# power.net
KiCad netlist of a schematic drawn in EAGLE
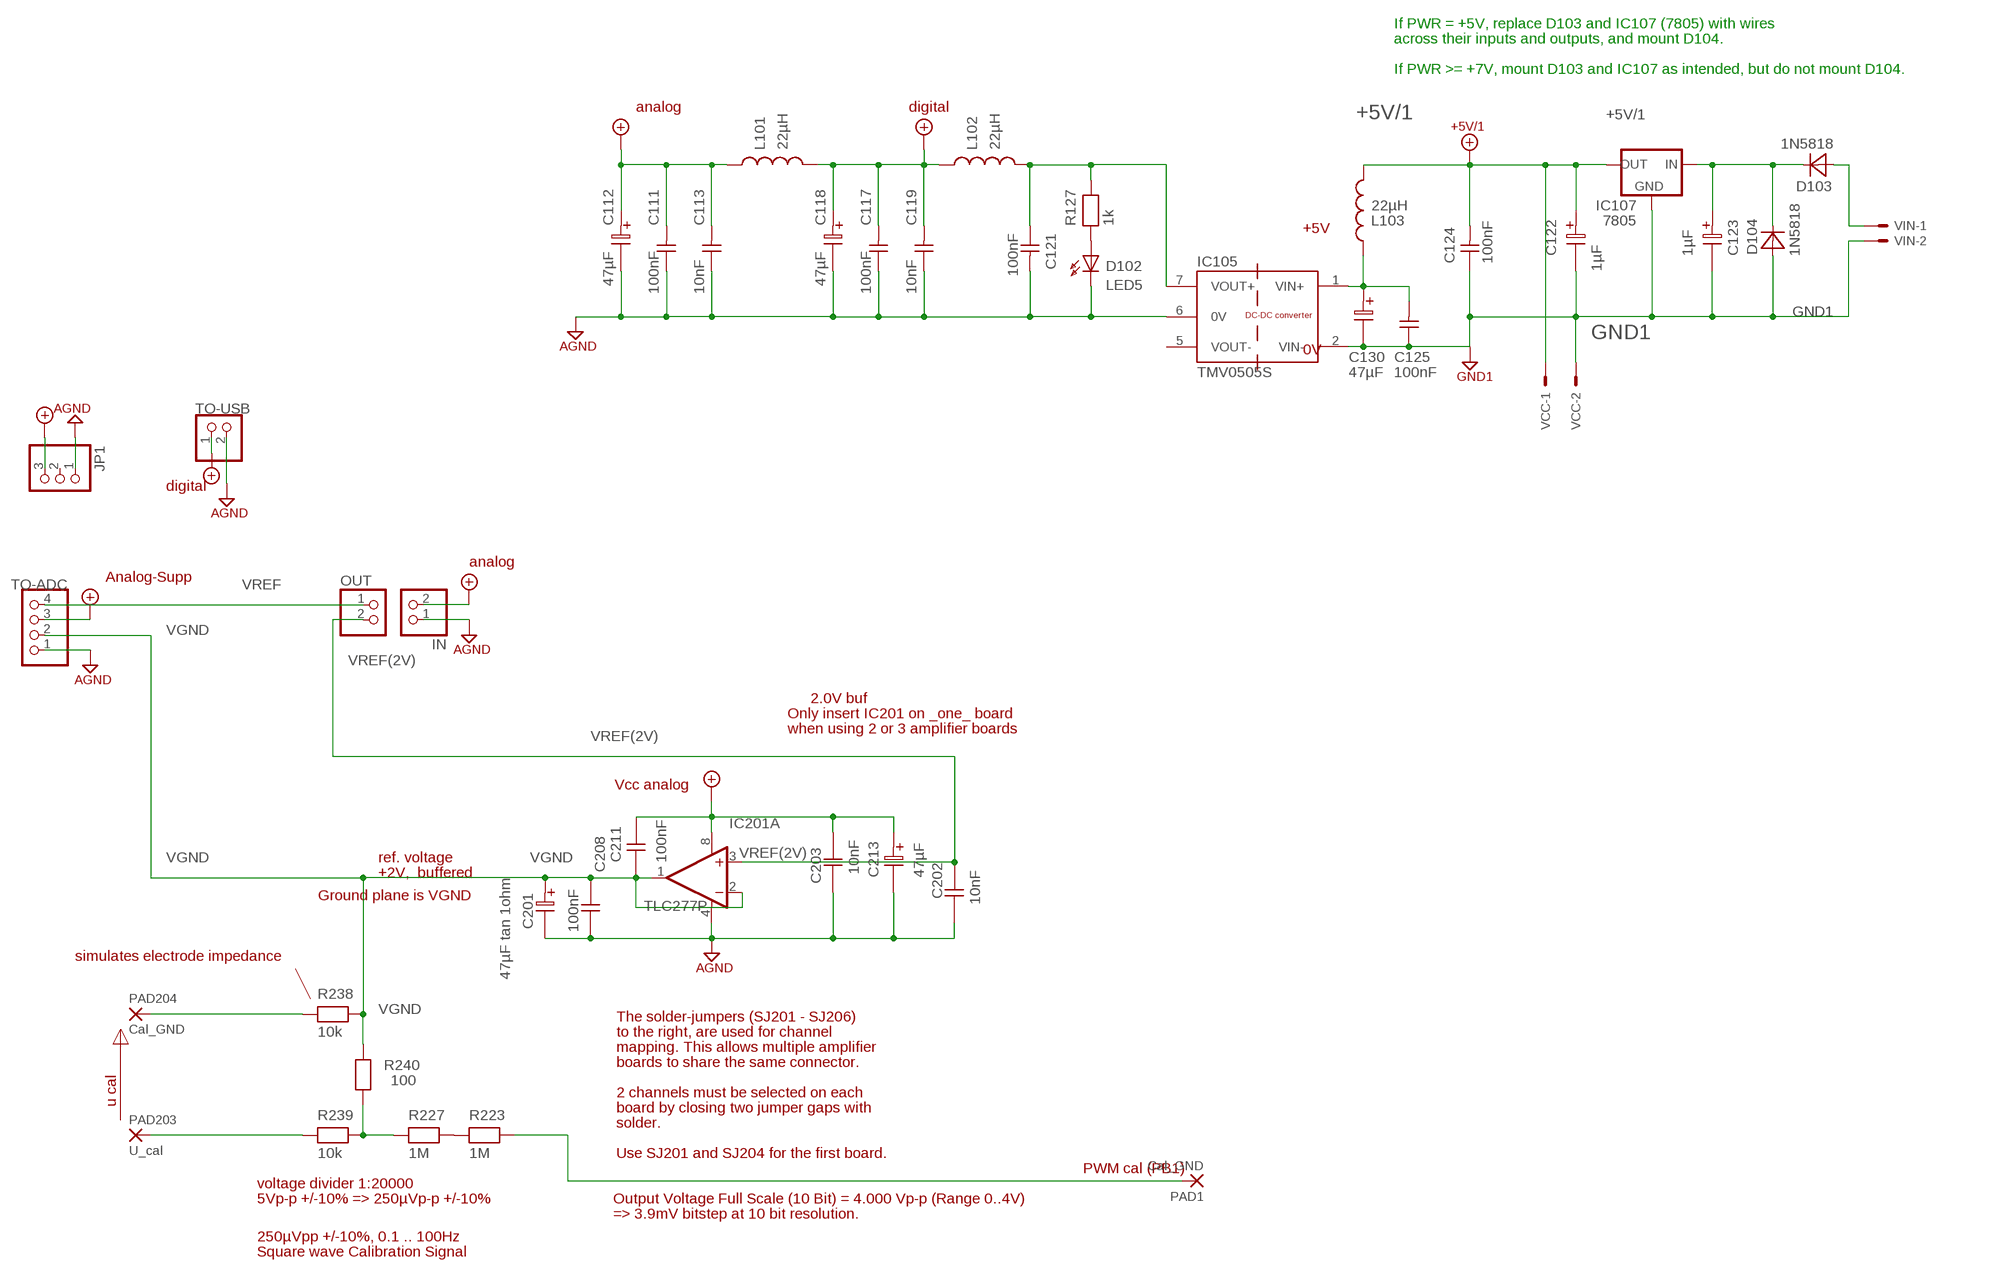
[diagram p0: schematic, sheet 1]

(export (version "E")
  (design (tool "Eeschema 10.0.6"))
  (components
    (comp (ref "C111")
      (value "100nF")
      (footprint "eagle-import:C-5")
      (libsource (lib "eagle-import") (part "CAPNP-5"))
    )
    (comp (ref "C112")
      (value "47µF")
      (footprint "eagle-import:EL25B")
      (libsource (lib "eagle-import") (part "discrete_211_ELC-5"))
    )
    (comp (ref "C113")
      (value "10nF")
      (footprint "eagle-import:C-5")
      (libsource (lib "eagle-import") (part "CAPNP-5"))
    )
    (comp (ref "C117")
      (value "100nF")
      (footprint "eagle-import:C-5")
      (libsource (lib "eagle-import") (part "CAPNP-5"))
    )
    (comp (ref "C118")
      (value "47µF")
      (footprint "eagle-import:EL25B")
      (libsource (lib "eagle-import") (part "discrete_211_ELC-5"))
    )
    (comp (ref "C119")
      (value "10nF")
      (footprint "eagle-import:C-5")
      (libsource (lib "eagle-import") (part "CAPNP-5"))
    )
    (comp (ref "C121")
      (value "100nF")
      (footprint "eagle-import:C-5@1")
      (libsource (lib "eagle-import") (part "discrete_211_CAPNP-5@2"))
    )
    (comp (ref "C122")
      (value "1µF")
      (footprint "eagle-import:EL25B")
      (libsource (lib "eagle-import") (part "ELC-2,5"))
    )
    (comp (ref "C123")
      (value "1µF")
      (footprint "eagle-import:EL25B")
      (libsource (lib "eagle-import") (part "ELC-2,5"))
    )
    (comp (ref "C124")
      (value "100nF")
      (footprint "eagle-import:C-5@1")
      (libsource (lib "eagle-import") (part "discrete_211_CAPNP-5@2"))
    )
    (comp (ref "C125")
      (value "100nF")
      (footprint "eagle-import:C-5")
      (libsource (lib "eagle-import") (part "CAPNP-5"))
    )
    (comp (ref "C130")
      (value "47µF")
      (footprint "eagle-import:EL25B")
      (libsource (lib "eagle-import") (part "discrete_211_ELC-5"))
    )
    (comp (ref "C201")
      (value "47µF tan 1ohm")
      (footprint "eagle-import:EL25B")
      (libsource (lib "eagle-import") (part "DISCRETE@3_ELC-2,5"))
    )
    (comp (ref "C202")
      (value "10nF")
      (footprint "eagle-import:C-5")
      (libsource (lib "eagle-import") (part "CAPNP-5@2"))
    )
    (comp (ref "C203")
      (value "10nF")
      (footprint "eagle-import:C-5")
      (libsource (lib "eagle-import") (part "CAPNP-7,5"))
    )
    (comp (ref "C208")
      (value "100nF")
      (footprint "eagle-import:C-5")
      (libsource (lib "eagle-import") (part "CAPNP-7,5"))
    )
    (comp (ref "C211")
      (value "100nF")
      (footprint "eagle-import:C-5")
      (libsource (lib "eagle-import") (part "CAPNP-5@2"))
    )
    (comp (ref "C213")
      (value "47µF")
      (footprint "eagle-import:EL25B")
      (libsource (lib "eagle-import") (part "ELC-5"))
    )
    (comp (ref "D102")
      (value "LED5")
      (footprint "eagle-import:LED5")
      (libsource (lib "eagle-import") (part "LED5"))
    )
    (comp (ref "D103")
      (value "1N5818")
      (footprint "eagle-import:D-12,5")
      (libsource (lib "eagle-import") (part "DIODE-12,5"))
    )
    (comp (ref "D104")
      (value "1N5818")
      (footprint "eagle-import:D-12,5")
      (libsource (lib "eagle-import") (part "DIODE-12,5"))
    )
    (comp (ref "IC105")
      (value "TMV0505S")
      (footprint "eagle-import:MEJDCDC-SC")
      (libsource (lib "eagle-import") (part "MEJ2D0505SC"))
    )
    (comp (ref "IC107")
      (value "7805")
      (footprint "eagle-import:78XXL_S")
      (libsource (lib "eagle-import") (part "78XXS"))
    )
    (comp (ref "IC201")
      (value "TLC277P")
      (footprint "eagle-import:DIL-08")
      (libsource (lib "eagle-import") (part "OPA2604AP"))
    )
    (comp (ref "IN")
      (value "PINHD-1X2")
      (footprint "eagle-import:1X02")
      (libsource (lib "eagle-import") (part "PINHD-1X2"))
    )
    (comp (ref "JP1")
      (value "PINHD-1X3")
      (footprint "eagle-import:1X03")
      (libsource (lib "eagle-import") (part "PINHD-1X3"))
    )
    (comp (ref "L101")
      (value "22µH")
      (footprint "eagle-import:R-12,5")
      (libsource (lib "eagle-import") (part "L-10"))
    )
    (comp (ref "L102")
      (value "22µH")
      (footprint "eagle-import:R-12,5")
      (libsource (lib "eagle-import") (part "L-10"))
    )
    (comp (ref "L103")
      (value "22µH")
      (footprint "eagle-import:R-12,5")
      (libsource (lib "eagle-import") (part "L-10"))
    )
    (comp (ref "OUT")
      (value "PINHD-1X2")
      (footprint "eagle-import:1X02")
      (libsource (lib "eagle-import") (part "PINHD-1X2"))
    )
    (comp (ref "PAD1")
      (value "Cal_GND")
      (footprint "eagle-import:WIREPAD1")
      (libsource (lib "eagle-import") (part "1,6/0,8"))
    )
    (comp (ref "PAD203")
      (value "U_cal")
      (footprint "eagle-import:WIREPAD1")
      (libsource (lib "eagle-import") (part "1,6/0,8"))
    )
    (comp (ref "PAD204")
      (value "Cal_GND")
      (footprint "eagle-import:WIREPAD1")
      (libsource (lib "eagle-import") (part "1,6/0,8"))
    )
    (comp (ref "R127")
      (value "1k")
      (footprint "eagle-import:R-10")
      (libsource (lib "eagle-import") (part "discrete_211_RESEU-10@2"))
    )
    (comp (ref "R223")
      (value "1M")
      (footprint "eagle-import:R-10")
      (libsource (lib "eagle-import") (part "RESEU-10@2"))
    )
    (comp (ref "R227")
      (value "1M")
      (footprint "eagle-import:R-10")
      (libsource (lib "eagle-import") (part "RESEU-10@2"))
    )
    (comp (ref "R238")
      (value "10k")
      (footprint "eagle-import:R-10")
      (libsource (lib "eagle-import") (part "RESEU-7,5"))
    )
    (comp (ref "R239")
      (value "10k")
      (footprint "eagle-import:R-10")
      (libsource (lib "eagle-import") (part "RESEU-7,5"))
    )
    (comp (ref "R240")
      (value "100")
      (footprint "eagle-import:R-10")
      (libsource (lib "eagle-import") (part "RESEU-7,5"))
    )
    (comp (ref "TO-ADC")
      (value "PINHD-1X4")
      (footprint "eagle-import:1X04")
      (libsource (lib "eagle-import") (part "PINHD-1X4"))
    )
    (comp (ref "TO-USB")
      (value "PINHD-1X2")
      (footprint "eagle-import:1X02")
      (libsource (lib "eagle-import") (part "PINHD-1X2"))
    )
    (comp (ref "VCC")
      (value "87758-0216")
      (footprint "eagle-import:87758-0216")
      (fields (field (name "MF") "MOLEX"))
      (libsource (lib "eagle-import") (part "87758-0216"))
    )
    (comp (ref "VIN")
      (value "22-23-2021")
      (footprint "eagle-import:22-23-2021")
      (fields (field (name "MF") "MOLEX"))
      (libsource (lib "eagle-import") (part "22-23-2021"))
    )
  )
  (nets
    (net (code "1") (name "+5V{slash}1") (class "Default")
      (node (ref "C122") (pin "1") (pinfunction "1_1") (pintype "passive"))
      (node (ref "C124") (pin "2") (pinfunction "2_2") (pintype "passive"))
      (node (ref "IC107") (pin "OUT") (pinfunction "OUT_OUT") (pintype "passive"))
      (node (ref "L103") (pin "2") (pinfunction "2_2") (pintype "passive"))
      (node (ref "VCC") (pin "1") (pinfunction "S_1") (pintype "passive"))
    )
    (net (code "2") (name "+5V{slash}2") (class "Default")
      (node (ref "C111") (pin "2") (pinfunction "2_2") (pintype "passive"))
      (node (ref "C112") (pin "1") (pinfunction "1_1") (pintype "passive"))
      (node (ref "C113") (pin "2") (pinfunction "2_2") (pintype "passive"))
      (node (ref "C203") (pin "1") (pinfunction "1_1") (pintype "passive"))
      (node (ref "C211") (pin "2") (pinfunction "2_2") (pintype "passive"))
      (node (ref "C213") (pin "1") (pinfunction "1_1") (pintype "passive"))
      (node (ref "IC201") (pin "8") (pinfunction "V+_8") (pintype "power_in"))
      (node (ref "IN") (pin "2") (pinfunction "2_2") (pintype "passive"))
      (node (ref "L101") (pin "1") (pinfunction "1_1") (pintype "passive"))
      (node (ref "TO-ADC") (pin "3") (pinfunction "3_3") (pintype "passive"))
    )
    (net (code "3") (name "+5V{slash}3") (class "Default")
      (node (ref "C117") (pin "2") (pinfunction "2_2") (pintype "passive"))
      (node (ref "C118") (pin "1") (pinfunction "1_1") (pintype "passive"))
      (node (ref "C119") (pin "2") (pinfunction "2_2") (pintype "passive"))
      (node (ref "JP1") (pin "3") (pinfunction "3_3") (pintype "passive"))
      (node (ref "L101") (pin "2") (pinfunction "2_2") (pintype "passive"))
      (node (ref "L102") (pin "1") (pinfunction "1_1") (pintype "passive"))
      (node (ref "TO-USB") (pin "1") (pinfunction "1_1") (pintype "passive"))
    )
    (net (code "4") (name "/VGND") (class "Default")
      (node (ref "C201") (pin "1") (pinfunction "1_1") (pintype "passive"))
      (node (ref "C208") (pin "1") (pinfunction "1_1") (pintype "passive"))
      (node (ref "C211") (pin "1") (pinfunction "1_1") (pintype "passive"))
      (node (ref "IC201") (pin "1") (pinfunction "OUT_1") (pintype "output"))
      (node (ref "IC201") (pin "2") (pinfunction "-IN_2") (pintype "input"))
      (node (ref "R238") (pin "2") (pinfunction "2_2") (pintype "passive"))
      (node (ref "R240") (pin "1") (pinfunction "1_1") (pintype "passive"))
      (node (ref "TO-ADC") (pin "2") (pinfunction "2_2") (pintype "passive"))
    )
    (net (code "5") (name "/VOUT-") (class "Default")
      (node (ref "IC105") (pin "5") (pinfunction "VOUT-_5") (pintype "power_in"))
    )
    (net (code "6") (name "/VREF") (class "Default")
      (node (ref "OUT") (pin "1") (pinfunction "1_1") (pintype "passive"))
      (node (ref "TO-ADC") (pin "4") (pinfunction "4_4") (pintype "passive"))
    )
    (net (code "7") (name "/VREF(2V)") (class "Default")
      (node (ref "C202") (pin "1") (pinfunction "1_1") (pintype "passive"))
      (node (ref "IC201") (pin "3") (pinfunction "+IN_3") (pintype "input"))
      (node (ref "OUT") (pin "2") (pinfunction "2_2") (pintype "passive"))
    )
    (net (code "8") (name "AGND") (class "Default")
      (node (ref "C111") (pin "1") (pinfunction "1_1") (pintype "passive"))
      (node (ref "C112") (pin "2") (pinfunction "2_2") (pintype "passive"))
      (node (ref "C113") (pin "1") (pinfunction "1_1") (pintype "passive"))
      (node (ref "C117") (pin "1") (pinfunction "1_1") (pintype "passive"))
      (node (ref "C118") (pin "2") (pinfunction "2_2") (pintype "passive"))
      (node (ref "C119") (pin "1") (pinfunction "1_1") (pintype "passive"))
      (node (ref "C121") (pin "2") (pinfunction "2_2") (pintype "passive"))
      (node (ref "C201") (pin "2") (pinfunction "2_2") (pintype "passive"))
      (node (ref "C202") (pin "2") (pinfunction "2_2") (pintype "passive"))
      (node (ref "C203") (pin "2") (pinfunction "2_2") (pintype "passive"))
      (node (ref "C208") (pin "2") (pinfunction "2_2") (pintype "passive"))
      (node (ref "C213") (pin "2") (pinfunction "2_2") (pintype "passive"))
      (node (ref "D102") (pin "K") (pinfunction "K_K") (pintype "passive"))
      (node (ref "IC105") (pin "6") (pinfunction "0V_6") (pintype "power_in"))
      (node (ref "IC201") (pin "4") (pinfunction "V-_4") (pintype "power_in"))
      (node (ref "IN") (pin "1") (pinfunction "1_1") (pintype "passive"))
      (node (ref "JP1") (pin "1") (pinfunction "1_1") (pintype "passive"))
      (node (ref "TO-ADC") (pin "1") (pinfunction "1_1") (pintype "passive"))
      (node (ref "TO-USB") (pin "2") (pinfunction "2_2") (pintype "passive"))
    )
    (net (code "9") (name "GND1") (class "Default")
      (node (ref "C122") (pin "2") (pinfunction "2_2") (pintype "passive"))
      (node (ref "C123") (pin "2") (pinfunction "2_2") (pintype "passive"))
      (node (ref "C124") (pin "1") (pinfunction "1_1") (pintype "passive"))
      (node (ref "C125") (pin "1") (pinfunction "1_1") (pintype "passive"))
      (node (ref "C130") (pin "2") (pinfunction "2_2") (pintype "passive"))
      (node (ref "D104") (pin "1") (pinfunction "A_1") (pintype "passive"))
      (node (ref "IC105") (pin "2") (pinfunction "VIN-_2") (pintype "power_in"))
      (node (ref "IC107") (pin "GND") (pinfunction "GND_GND") (pintype "input"))
      (node (ref "VCC") (pin "2") (pinfunction "S_2") (pintype "passive"))
      (node (ref "VIN") (pin "2") (pinfunction "S_2") (pintype "passive"))
    )
    (net (code "10") (name "Net-(D102-PadA)") (class "Default")
      (node (ref "D102") (pin "A") (pinfunction "A_A") (pintype "passive"))
      (node (ref "R127") (pin "1") (pinfunction "1_1") (pintype "passive"))
    )
    (net (code "11") (name "Net-(D103-A)") (class "Default")
      (node (ref "D103") (pin "1") (pinfunction "A_1") (pintype "passive"))
      (node (ref "VIN") (pin "1") (pinfunction "S_1") (pintype "passive"))
    )
    (net (code "12") (name "Net-(D103-K)") (class "Default")
      (node (ref "C123") (pin "1") (pinfunction "1_1") (pintype "passive"))
      (node (ref "D103") (pin "2") (pinfunction "K_2") (pintype "passive"))
      (node (ref "D104") (pin "2") (pinfunction "K_2") (pintype "passive"))
      (node (ref "IC107") (pin "IN") (pinfunction "IN_IN") (pintype "input"))
    )
    (net (code "13") (name "Net-(IC105-VIN+)") (class "Default")
      (node (ref "C125") (pin "2") (pinfunction "2_2") (pintype "passive"))
      (node (ref "C130") (pin "1") (pinfunction "1_1") (pintype "passive"))
      (node (ref "IC105") (pin "1") (pinfunction "VIN+_1") (pintype "power_in"))
      (node (ref "L103") (pin "1") (pinfunction "1_1") (pintype "passive"))
    )
    (net (code "14") (name "Net-(IC105-VOUT+)") (class "Default")
      (node (ref "C121") (pin "1") (pinfunction "1_1") (pintype "passive"))
      (node (ref "IC105") (pin "7") (pinfunction "VOUT+_7") (pintype "power_in"))
      (node (ref "L102") (pin "2") (pinfunction "2_2") (pintype "passive"))
      (node (ref "R127") (pin "2") (pinfunction "2_2") (pintype "passive"))
    )
    (net (code "15") (name "Net-(PAD1-P)") (class "Default")
      (node (ref "PAD1") (pin "1") (pinfunction "P_1") (pintype "passive"))
      (node (ref "R223") (pin "2") (pinfunction "2_2") (pintype "passive"))
    )
    (net (code "16") (name "Net-(PAD203-P)") (class "Default")
      (node (ref "PAD203") (pin "1") (pinfunction "P_1") (pintype "passive"))
      (node (ref "R239") (pin "1") (pinfunction "1_1") (pintype "passive"))
    )
    (net (code "17") (name "Net-(PAD204-P)") (class "Default")
      (node (ref "PAD204") (pin "1") (pinfunction "P_1") (pintype "passive"))
      (node (ref "R238") (pin "1") (pinfunction "1_1") (pintype "passive"))
    )
    (net (code "18") (name "Net-(R223-Pad1)") (class "Default")
      (node (ref "R223") (pin "1") (pinfunction "1_1") (pintype "passive"))
      (node (ref "R227") (pin "2") (pinfunction "2_2") (pintype "passive"))
    )
    (net (code "19") (name "Net-(R227-Pad1)") (class "Default")
      (node (ref "R227") (pin "1") (pinfunction "1_1") (pintype "passive"))
      (node (ref "R239") (pin "2") (pinfunction "2_2") (pintype "passive"))
      (node (ref "R240") (pin "2") (pinfunction "2_2") (pintype "passive"))
    )
    (net (code "20") (name "unconnected-(JP1-Pad2)") (class "Default")
      (node (ref "JP1") (pin "2") (pinfunction "2_2") (pintype "passive"))
    )
  )
)
